# Aquarium_Controller_Diy_Board.net
KiCad netlist of a schematic drawn in EAGLE
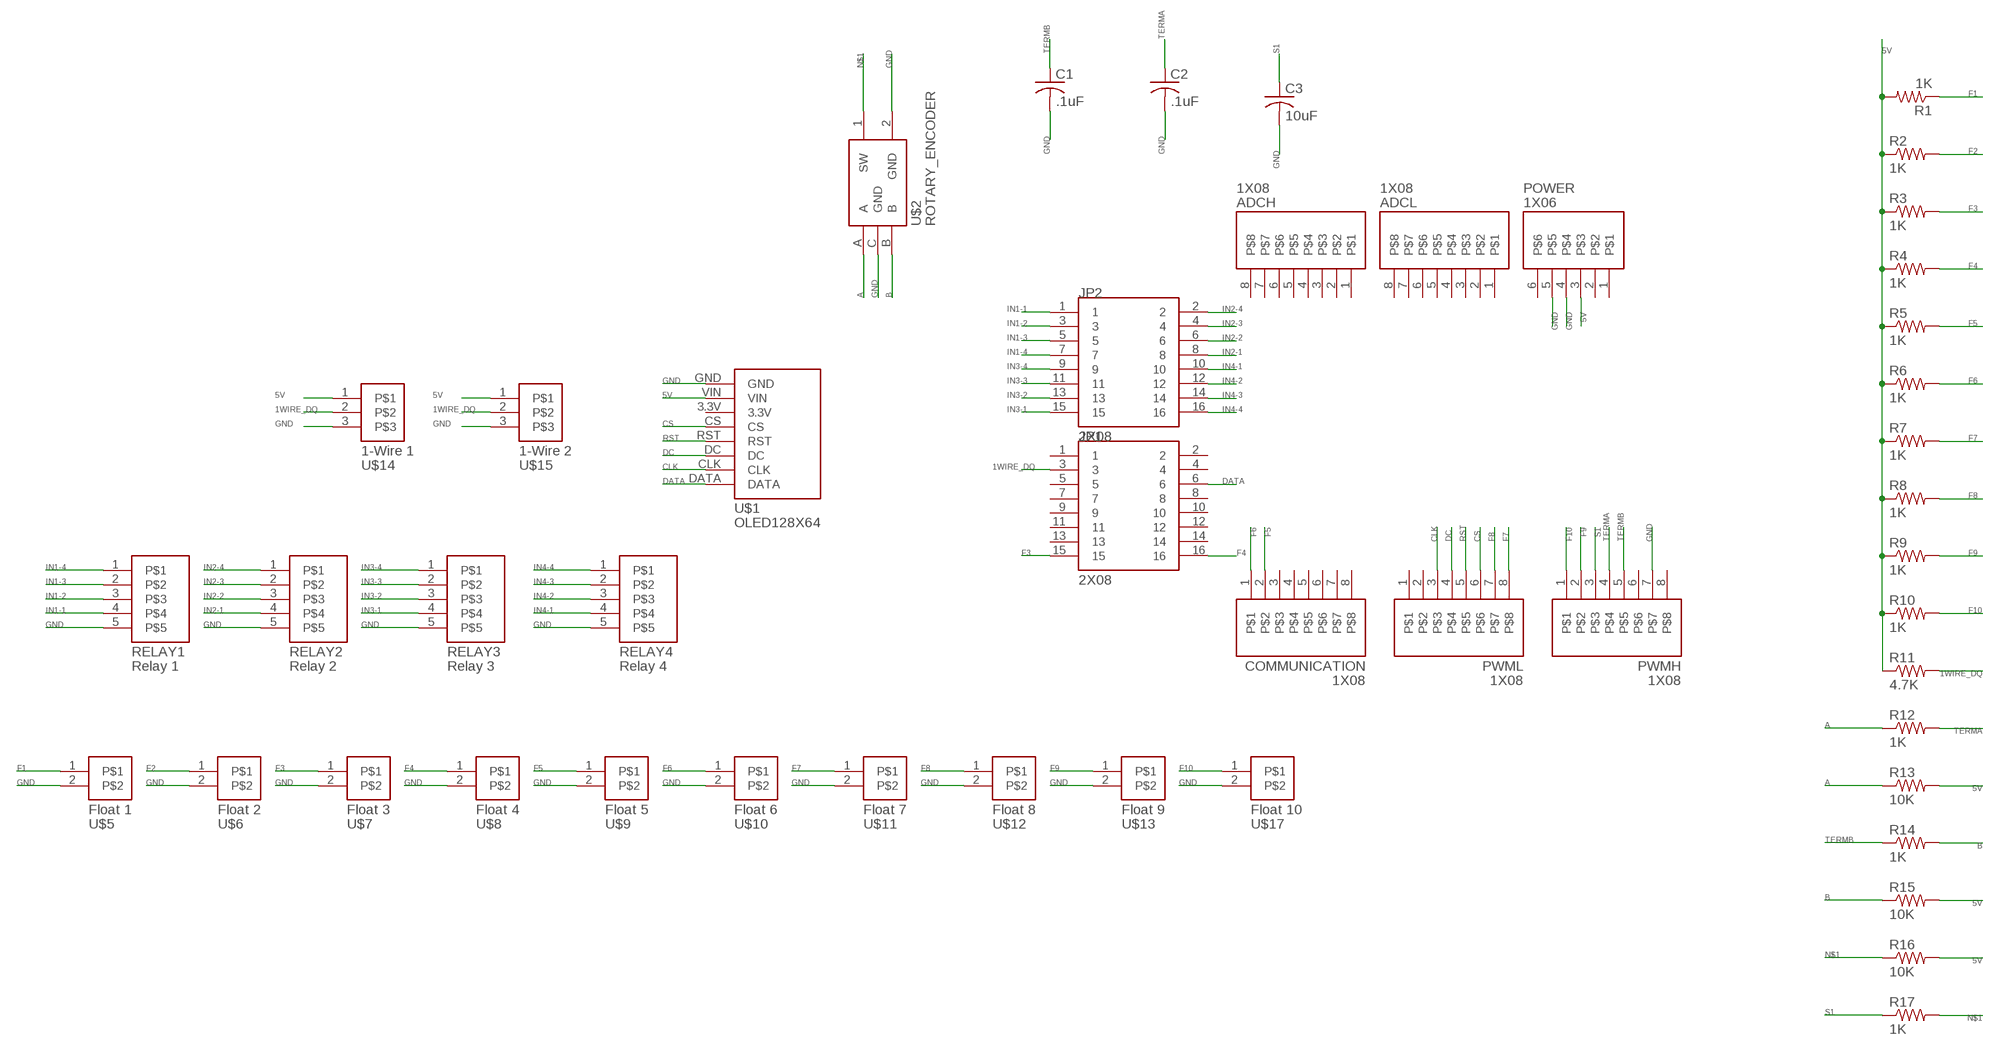
[diagram p0: schematic, sheet 1]

(export (version "E")
  (design (tool "Eeschema 10.0.6"))
  (components
    (comp (ref "ADCH")
      (value "1X08")
      (footprint "eagle-import:1X08_SMT")
      (libsource (lib "eagle-import") (part "1X08"))
    )
    (comp (ref "ADCL")
      (value "1X08")
      (footprint "eagle-import:1X08_SMT")
      (libsource (lib "eagle-import") (part "1X08"))
    )
    (comp (ref "C1")
      (value ".1uF")
      (footprint "eagle-import:C0805K")
      (libsource (lib "eagle-import") (part "C-USC0805K"))
    )
    (comp (ref "C2")
      (value ".1uF")
      (footprint "eagle-import:C0805K")
      (libsource (lib "eagle-import") (part "resistor_C-USC0805K"))
    )
    (comp (ref "C3")
      (value "10uF")
      (footprint "eagle-import:C0805K")
      (libsource (lib "eagle-import") (part "resistor_C-USC0805K"))
    )
    (comp (ref "COMMUNICATION")
      (value "1X08")
      (footprint "eagle-import:1X08_SMT")
      (libsource (lib "eagle-import") (part "1X08"))
    )
    (comp (ref "JP1")
      (value "2X08")
      (footprint "eagle-import:2X08_SMT")
      (libsource (lib "eagle-import") (part "2X08"))
    )
    (comp (ref "JP2")
      (value "2X08")
      (footprint "eagle-import:2X08_SMT")
      (libsource (lib "eagle-import") (part "2X08"))
    )
    (comp (ref "POWER")
      (value "1X06")
      (footprint "eagle-import:1X06_SMT")
      (libsource (lib "eagle-import") (part "1X06"))
    )
    (comp (ref "PWMH")
      (value "1X08")
      (footprint "eagle-import:1X08_SMT")
      (libsource (lib "eagle-import") (part "1X08"))
    )
    (comp (ref "PWML")
      (value "1X08")
      (footprint "eagle-import:1X08_SMT")
      (libsource (lib "eagle-import") (part "1X08"))
    )
    (comp (ref "R1")
      (value "1K")
      (footprint "eagle-import:R0805")
      (libsource (lib "eagle-import") (part "R-US_R0805"))
    )
    (comp (ref "R2")
      (value "1K")
      (footprint "eagle-import:R0805")
      (libsource (lib "eagle-import") (part "R-US_R0805"))
    )
    (comp (ref "R3")
      (value "1K")
      (footprint "eagle-import:R0805")
      (libsource (lib "eagle-import") (part "R-US_R0805"))
    )
    (comp (ref "R4")
      (value "1K")
      (footprint "eagle-import:R0805")
      (libsource (lib "eagle-import") (part "R-US_R0805"))
    )
    (comp (ref "R5")
      (value "1K")
      (footprint "eagle-import:R0805")
      (libsource (lib "eagle-import") (part "R-US_R0805"))
    )
    (comp (ref "R6")
      (value "1K")
      (footprint "eagle-import:R0805")
      (libsource (lib "eagle-import") (part "R-US_R0805"))
    )
    (comp (ref "R7")
      (value "1K")
      (footprint "eagle-import:R0805")
      (libsource (lib "eagle-import") (part "R-US_R0805"))
    )
    (comp (ref "R8")
      (value "1K")
      (footprint "eagle-import:R0805")
      (libsource (lib "eagle-import") (part "R-US_R0805"))
    )
    (comp (ref "R9")
      (value "1K")
      (footprint "eagle-import:R0805")
      (libsource (lib "eagle-import") (part "R-US_R0805"))
    )
    (comp (ref "R10")
      (value "1K")
      (footprint "eagle-import:R0805")
      (libsource (lib "eagle-import") (part "R-US_R0805"))
    )
    (comp (ref "R11")
      (value "4.7K")
      (footprint "eagle-import:R0805")
      (libsource (lib "eagle-import") (part "R-US_R0805"))
    )
    (comp (ref "R12")
      (value "1K")
      (footprint "eagle-import:R0805")
      (libsource (lib "eagle-import") (part "R-US_R0805"))
    )
    (comp (ref "R13")
      (value "10K")
      (footprint "eagle-import:R0805")
      (libsource (lib "eagle-import") (part "R-US_R0805"))
    )
    (comp (ref "R14")
      (value "1K")
      (footprint "eagle-import:R0805")
      (libsource (lib "eagle-import") (part "R-US_R0805"))
    )
    (comp (ref "R15")
      (value "10K")
      (footprint "eagle-import:R0805")
      (libsource (lib "eagle-import") (part "R-US_R0805"))
    )
    (comp (ref "R16")
      (value "10K")
      (footprint "eagle-import:R0805")
      (libsource (lib "eagle-import") (part "R-US_R0805"))
    )
    (comp (ref "R17")
      (value "1K")
      (footprint "eagle-import:R0805")
      (libsource (lib "eagle-import") (part "R-US_R0805"))
    )
    (comp (ref "RELAY1")
      (value "Relay 1")
      (footprint "eagle-import:5PIN-MOLEX-HEADER-W-PEGS")
      (libsource (lib "eagle-import") (part "5PIN"))
    )
    (comp (ref "RELAY2")
      (value "Relay 2")
      (footprint "eagle-import:5PIN-MOLEX-HEADER-W-PEGS")
      (libsource (lib "eagle-import") (part "5PIN"))
    )
    (comp (ref "RELAY3")
      (value "Relay 3")
      (footprint "eagle-import:5PIN-MOLEX-HEADER-W-PEGS")
      (libsource (lib "eagle-import") (part "5PIN"))
    )
    (comp (ref "RELAY4")
      (value "Relay 4")
      (footprint "eagle-import:5PIN-MOLEX-HEADER-W-PEGS")
      (libsource (lib "eagle-import") (part "5PIN"))
    )
    (comp (ref "U$1")
      (value "OLED128X64")
      (footprint "eagle-import:OLED128X64")
      (libsource (lib "eagle-import") (part "OLED128X64"))
    )
    (comp (ref "U$2")
      (value "ROTARY_ENCODER")
      (footprint "eagle-import:PEC11-4215F-S24")
      (libsource (lib "eagle-import") (part "PEC11-4215F-S24"))
    )
    (comp (ref "U$5")
      (value "Float 1")
      (footprint "eagle-import:2PIN-MOLEX-HEADER-W-PEGS")
      (libsource (lib "eagle-import") (part "2PIN"))
    )
    (comp (ref "U$6")
      (value "Float 2")
      (footprint "eagle-import:2PIN-MOLEX-HEADER-W-PEGS")
      (libsource (lib "eagle-import") (part "2PIN"))
    )
    (comp (ref "U$7")
      (value "Float 3")
      (footprint "eagle-import:2PIN-MOLEX-HEADER-W-PEGS")
      (libsource (lib "eagle-import") (part "2PIN"))
    )
    (comp (ref "U$8")
      (value "Float 4")
      (footprint "eagle-import:2PIN-MOLEX-HEADER-W-PEGS")
      (libsource (lib "eagle-import") (part "2PIN"))
    )
    (comp (ref "U$9")
      (value "Float 5")
      (footprint "eagle-import:2PIN-MOLEX-HEADER-W-PEGS")
      (libsource (lib "eagle-import") (part "2PIN"))
    )
    (comp (ref "U$10")
      (value "Float 6")
      (footprint "eagle-import:2PIN-MOLEX-HEADER-W-PEGS")
      (libsource (lib "eagle-import") (part "2PIN"))
    )
    (comp (ref "U$11")
      (value "Float 7")
      (footprint "eagle-import:2PIN-MOLEX-HEADER-W-PEGS")
      (libsource (lib "eagle-import") (part "2PIN"))
    )
    (comp (ref "U$12")
      (value "Float 8")
      (footprint "eagle-import:2PIN-MOLEX-HEADER-W-PEGS")
      (libsource (lib "eagle-import") (part "2PIN"))
    )
    (comp (ref "U$13")
      (value "Float 9")
      (footprint "eagle-import:2PIN-MOLEX-HEADER-W-PEGS")
      (libsource (lib "eagle-import") (part "2PIN"))
    )
    (comp (ref "U$14")
      (value "1-Wire 1")
      (footprint "eagle-import:3PIN-MOLEX-HEADER-W-PEGS")
      (libsource (lib "eagle-import") (part "3PIN"))
    )
    (comp (ref "U$15")
      (value "1-Wire 2")
      (footprint "eagle-import:3PIN-MOLEX-HEADER-W-PEGS")
      (libsource (lib "eagle-import") (part "3PIN"))
    )
    (comp (ref "U$17")
      (value "Float 10")
      (footprint "eagle-import:2PIN-MOLEX-HEADER-W-PEGS")
      (libsource (lib "eagle-import") (part "2PIN"))
    )
  )
  (nets
    (net (code "1") (name "/1WIRE_DQ") (class "Default")
      (node (ref "JP1") (pin "3") (pinfunction "3_3") (pintype "bidirectional"))
      (node (ref "R11") (pin "2") (pinfunction "2_2") (pintype "passive"))
      (node (ref "U$14") (pin "2") (pinfunction "P$2_2") (pintype "bidirectional"))
      (node (ref "U$15") (pin "2") (pinfunction "P$2_2") (pintype "bidirectional"))
    )
    (net (code "2") (name "/5V") (class "Default")
      (node (ref "POWER") (pin "3") (pinfunction "P$3_3") (pintype "bidirectional"))
      (node (ref "R1") (pin "2") (pinfunction "2_2") (pintype "passive"))
      (node (ref "R10") (pin "1") (pinfunction "1_1") (pintype "passive"))
      (node (ref "R11") (pin "1") (pinfunction "1_1") (pintype "passive"))
      (node (ref "R13") (pin "2") (pinfunction "2_2") (pintype "passive"))
      (node (ref "R15") (pin "2") (pinfunction "2_2") (pintype "passive"))
      (node (ref "R16") (pin "2") (pinfunction "2_2") (pintype "passive"))
      (node (ref "R2") (pin "1") (pinfunction "1_1") (pintype "passive"))
      (node (ref "R3") (pin "1") (pinfunction "1_1") (pintype "passive"))
      (node (ref "R4") (pin "1") (pinfunction "1_1") (pintype "passive"))
      (node (ref "R5") (pin "1") (pinfunction "1_1") (pintype "passive"))
      (node (ref "R6") (pin "1") (pinfunction "1_1") (pintype "passive"))
      (node (ref "R7") (pin "1") (pinfunction "1_1") (pintype "passive"))
      (node (ref "R8") (pin "1") (pinfunction "1_1") (pintype "passive"))
      (node (ref "R9") (pin "1") (pinfunction "1_1") (pintype "passive"))
      (node (ref "U$1") (pin "VIN") (pinfunction "VIN_VIN") (pintype "bidirectional"))
      (node (ref "U$14") (pin "1") (pinfunction "P$1_1") (pintype "bidirectional"))
      (node (ref "U$15") (pin "1") (pinfunction "P$1_1") (pintype "bidirectional"))
    )
    (net (code "3") (name "/A") (class "Default")
      (node (ref "R12") (pin "1") (pinfunction "1_1") (pintype "passive"))
      (node (ref "R13") (pin "1") (pinfunction "1_1") (pintype "passive"))
      (node (ref "U$2") (pin "A") (pinfunction "A_A") (pintype "bidirectional"))
    )
    (net (code "4") (name "/B") (class "Default")
      (node (ref "R14") (pin "2") (pinfunction "2_2") (pintype "passive"))
      (node (ref "R15") (pin "1") (pinfunction "1_1") (pintype "passive"))
      (node (ref "U$2") (pin "B") (pinfunction "B_B") (pintype "bidirectional"))
    )
    (net (code "5") (name "/CLK") (class "Default")
      (node (ref "PWML") (pin "3") (pinfunction "P$3_3") (pintype "bidirectional"))
      (node (ref "U$1") (pin "CLK") (pinfunction "CLK_CLK") (pintype "bidirectional"))
    )
    (net (code "6") (name "/CS") (class "Default")
      (node (ref "PWML") (pin "6") (pinfunction "P$6_6") (pintype "bidirectional"))
      (node (ref "U$1") (pin "CS") (pinfunction "CS_CS") (pintype "bidirectional"))
    )
    (net (code "7") (name "/DATA") (class "Default")
      (node (ref "JP1") (pin "6") (pinfunction "6_6") (pintype "bidirectional"))
      (node (ref "U$1") (pin "DATA") (pinfunction "DATA_DATA") (pintype "bidirectional"))
    )
    (net (code "8") (name "/DC") (class "Default")
      (node (ref "PWML") (pin "4") (pinfunction "P$4_4") (pintype "bidirectional"))
      (node (ref "U$1") (pin "DC") (pinfunction "DC_DC") (pintype "bidirectional"))
    )
    (net (code "9") (name "/F1") (class "Default")
      (node (ref "R1") (pin "1") (pinfunction "1_1") (pintype "passive"))
      (node (ref "U$5") (pin "1") (pinfunction "P$1_1") (pintype "bidirectional"))
    )
    (net (code "10") (name "/F2") (class "Default")
      (node (ref "R2") (pin "2") (pinfunction "2_2") (pintype "passive"))
      (node (ref "U$6") (pin "1") (pinfunction "P$1_1") (pintype "bidirectional"))
    )
    (net (code "11") (name "/F3") (class "Default")
      (node (ref "JP1") (pin "15") (pinfunction "15_15") (pintype "bidirectional"))
      (node (ref "R3") (pin "2") (pinfunction "2_2") (pintype "passive"))
      (node (ref "U$7") (pin "1") (pinfunction "P$1_1") (pintype "bidirectional"))
    )
    (net (code "12") (name "/F4") (class "Default")
      (node (ref "JP1") (pin "16") (pinfunction "16_16") (pintype "bidirectional"))
      (node (ref "R4") (pin "2") (pinfunction "2_2") (pintype "passive"))
      (node (ref "U$8") (pin "1") (pinfunction "P$1_1") (pintype "bidirectional"))
    )
    (net (code "13") (name "/F5") (class "Default")
      (node (ref "COMMUNICATION") (pin "2") (pinfunction "P$2_2") (pintype "bidirectional"))
      (node (ref "R5") (pin "2") (pinfunction "2_2") (pintype "passive"))
      (node (ref "U$9") (pin "1") (pinfunction "P$1_1") (pintype "bidirectional"))
    )
    (net (code "14") (name "/F6") (class "Default")
      (node (ref "COMMUNICATION") (pin "1") (pinfunction "P$1_1") (pintype "bidirectional"))
      (node (ref "R6") (pin "2") (pinfunction "2_2") (pintype "passive"))
      (node (ref "U$10") (pin "1") (pinfunction "P$1_1") (pintype "bidirectional"))
    )
    (net (code "15") (name "/F7") (class "Default")
      (node (ref "PWML") (pin "8") (pinfunction "P$8_8") (pintype "bidirectional"))
      (node (ref "R7") (pin "2") (pinfunction "2_2") (pintype "passive"))
      (node (ref "U$11") (pin "1") (pinfunction "P$1_1") (pintype "bidirectional"))
    )
    (net (code "16") (name "/F8") (class "Default")
      (node (ref "PWML") (pin "7") (pinfunction "P$7_7") (pintype "bidirectional"))
      (node (ref "R8") (pin "2") (pinfunction "2_2") (pintype "passive"))
      (node (ref "U$12") (pin "1") (pinfunction "P$1_1") (pintype "bidirectional"))
    )
    (net (code "17") (name "/F9") (class "Default")
      (node (ref "PWMH") (pin "2") (pinfunction "P$2_2") (pintype "bidirectional"))
      (node (ref "R9") (pin "2") (pinfunction "2_2") (pintype "passive"))
      (node (ref "U$13") (pin "1") (pinfunction "P$1_1") (pintype "bidirectional"))
    )
    (net (code "18") (name "/F10") (class "Default")
      (node (ref "PWMH") (pin "1") (pinfunction "P$1_1") (pintype "bidirectional"))
      (node (ref "R10") (pin "2") (pinfunction "2_2") (pintype "passive"))
      (node (ref "U$17") (pin "1") (pinfunction "P$1_1") (pintype "bidirectional"))
    )
    (net (code "19") (name "/GND") (class "Default")
      (node (ref "C1") (pin "2") (pinfunction "2_2") (pintype "passive"))
      (node (ref "C2") (pin "2") (pinfunction "2_2") (pintype "passive"))
      (node (ref "C3") (pin "2") (pinfunction "2_2") (pintype "passive"))
      (node (ref "POWER") (pin "4") (pinfunction "P$4_4") (pintype "bidirectional"))
      (node (ref "POWER") (pin "5") (pinfunction "P$5_5") (pintype "bidirectional"))
      (node (ref "PWMH") (pin "7") (pinfunction "P$7_7") (pintype "bidirectional"))
      (node (ref "RELAY1") (pin "5") (pinfunction "P$5_5") (pintype "bidirectional"))
      (node (ref "RELAY2") (pin "5") (pinfunction "P$5_5") (pintype "bidirectional"))
      (node (ref "RELAY3") (pin "5") (pinfunction "P$5_5") (pintype "bidirectional"))
      (node (ref "RELAY4") (pin "5") (pinfunction "P$5_5") (pintype "bidirectional"))
      (node (ref "U$1") (pin "GND") (pinfunction "GND_GND") (pintype "bidirectional"))
      (node (ref "U$10") (pin "2") (pinfunction "P$2_2") (pintype "bidirectional"))
      (node (ref "U$11") (pin "2") (pinfunction "P$2_2") (pintype "bidirectional"))
      (node (ref "U$12") (pin "2") (pinfunction "P$2_2") (pintype "bidirectional"))
      (node (ref "U$13") (pin "2") (pinfunction "P$2_2") (pintype "bidirectional"))
      (node (ref "U$14") (pin "3") (pinfunction "P$3_3") (pintype "bidirectional"))
      (node (ref "U$15") (pin "3") (pinfunction "P$3_3") (pintype "bidirectional"))
      (node (ref "U$17") (pin "2") (pinfunction "P$2_2") (pintype "bidirectional"))
      (node (ref "U$2") (pin "2") (pinfunction "GND_2") (pintype "bidirectional"))
      (node (ref "U$2") (pin "C") (pinfunction "GND_C") (pintype "bidirectional"))
      (node (ref "U$5") (pin "2") (pinfunction "P$2_2") (pintype "bidirectional"))
      (node (ref "U$6") (pin "2") (pinfunction "P$2_2") (pintype "bidirectional"))
      (node (ref "U$7") (pin "2") (pinfunction "P$2_2") (pintype "bidirectional"))
      (node (ref "U$8") (pin "2") (pinfunction "P$2_2") (pintype "bidirectional"))
      (node (ref "U$9") (pin "2") (pinfunction "P$2_2") (pintype "bidirectional"))
    )
    (net (code "20") (name "/IN1-1") (class "Default")
      (node (ref "JP2") (pin "1") (pinfunction "1_1") (pintype "bidirectional"))
      (node (ref "RELAY1") (pin "4") (pinfunction "P$4_4") (pintype "bidirectional"))
    )
    (net (code "21") (name "/IN1-2") (class "Default")
      (node (ref "JP2") (pin "3") (pinfunction "3_3") (pintype "bidirectional"))
      (node (ref "RELAY1") (pin "3") (pinfunction "P$3_3") (pintype "bidirectional"))
    )
    (net (code "22") (name "/IN1-3") (class "Default")
      (node (ref "JP2") (pin "5") (pinfunction "5_5") (pintype "bidirectional"))
      (node (ref "RELAY1") (pin "2") (pinfunction "P$2_2") (pintype "bidirectional"))
    )
    (net (code "23") (name "/IN1-4") (class "Default")
      (node (ref "JP2") (pin "7") (pinfunction "7_7") (pintype "bidirectional"))
      (node (ref "RELAY1") (pin "1") (pinfunction "P$1_1") (pintype "bidirectional"))
    )
    (net (code "24") (name "/IN2-1") (class "Default")
      (node (ref "JP2") (pin "8") (pinfunction "8_8") (pintype "bidirectional"))
      (node (ref "RELAY2") (pin "4") (pinfunction "P$4_4") (pintype "bidirectional"))
    )
    (net (code "25") (name "/IN2-2") (class "Default")
      (node (ref "JP2") (pin "6") (pinfunction "6_6") (pintype "bidirectional"))
      (node (ref "RELAY2") (pin "3") (pinfunction "P$3_3") (pintype "bidirectional"))
    )
    (net (code "26") (name "/IN2-3") (class "Default")
      (node (ref "JP2") (pin "4") (pinfunction "4_4") (pintype "bidirectional"))
      (node (ref "RELAY2") (pin "2") (pinfunction "P$2_2") (pintype "bidirectional"))
    )
    (net (code "27") (name "/IN2-4") (class "Default")
      (node (ref "JP2") (pin "2") (pinfunction "2_2") (pintype "bidirectional"))
      (node (ref "RELAY2") (pin "1") (pinfunction "P$1_1") (pintype "bidirectional"))
    )
    (net (code "28") (name "/IN3-1") (class "Default")
      (node (ref "JP2") (pin "15") (pinfunction "15_15") (pintype "bidirectional"))
      (node (ref "RELAY3") (pin "4") (pinfunction "P$4_4") (pintype "bidirectional"))
    )
    (net (code "29") (name "/IN3-2") (class "Default")
      (node (ref "JP2") (pin "13") (pinfunction "13_13") (pintype "bidirectional"))
      (node (ref "RELAY3") (pin "3") (pinfunction "P$3_3") (pintype "bidirectional"))
    )
    (net (code "30") (name "/IN3-3") (class "Default")
      (node (ref "JP2") (pin "11") (pinfunction "11_11") (pintype "bidirectional"))
      (node (ref "RELAY3") (pin "2") (pinfunction "P$2_2") (pintype "bidirectional"))
    )
    (net (code "31") (name "/IN3-4") (class "Default")
      (node (ref "JP2") (pin "9") (pinfunction "9_9") (pintype "bidirectional"))
      (node (ref "RELAY3") (pin "1") (pinfunction "P$1_1") (pintype "bidirectional"))
    )
    (net (code "32") (name "/IN4-1") (class "Default")
      (node (ref "JP2") (pin "10") (pinfunction "10_10") (pintype "bidirectional"))
      (node (ref "RELAY4") (pin "4") (pinfunction "P$4_4") (pintype "bidirectional"))
    )
    (net (code "33") (name "/IN4-2") (class "Default")
      (node (ref "JP2") (pin "12") (pinfunction "12_12") (pintype "bidirectional"))
      (node (ref "RELAY4") (pin "3") (pinfunction "P$3_3") (pintype "bidirectional"))
    )
    (net (code "34") (name "/IN4-3") (class "Default")
      (node (ref "JP2") (pin "14") (pinfunction "14_14") (pintype "bidirectional"))
      (node (ref "RELAY4") (pin "2") (pinfunction "P$2_2") (pintype "bidirectional"))
    )
    (net (code "35") (name "/IN4-4") (class "Default")
      (node (ref "JP2") (pin "16") (pinfunction "16_16") (pintype "bidirectional"))
      (node (ref "RELAY4") (pin "1") (pinfunction "P$1_1") (pintype "bidirectional"))
    )
    (net (code "36") (name "/N$1") (class "Default")
      (node (ref "R16") (pin "1") (pinfunction "1_1") (pintype "passive"))
      (node (ref "R17") (pin "2") (pinfunction "2_2") (pintype "passive"))
      (node (ref "U$2") (pin "1") (pinfunction "SW_1") (pintype "bidirectional"))
    )
    (net (code "37") (name "/RST") (class "Default")
      (node (ref "PWML") (pin "5") (pinfunction "P$5_5") (pintype "bidirectional"))
      (node (ref "U$1") (pin "RST") (pinfunction "RST_RST") (pintype "bidirectional"))
    )
    (net (code "38") (name "/S1") (class "Default")
      (node (ref "C3") (pin "1") (pinfunction "1_1") (pintype "passive"))
      (node (ref "PWMH") (pin "3") (pinfunction "P$3_3") (pintype "bidirectional"))
      (node (ref "R17") (pin "1") (pinfunction "1_1") (pintype "passive"))
    )
    (net (code "39") (name "/TERMA") (class "Default")
      (node (ref "C2") (pin "1") (pinfunction "1_1") (pintype "passive"))
      (node (ref "PWMH") (pin "4") (pinfunction "P$4_4") (pintype "bidirectional"))
      (node (ref "R12") (pin "2") (pinfunction "2_2") (pintype "passive"))
    )
    (net (code "40") (name "/TERMB") (class "Default")
      (node (ref "C1") (pin "1") (pinfunction "1_1") (pintype "passive"))
      (node (ref "PWMH") (pin "5") (pinfunction "P$5_5") (pintype "bidirectional"))
      (node (ref "R14") (pin "1") (pinfunction "1_1") (pintype "passive"))
    )
    (net (code "41") (name "unconnected-(ADCH-P$1-Pad1)") (class "Default")
      (node (ref "ADCH") (pin "1") (pinfunction "P$1_1") (pintype "bidirectional"))
    )
    (net (code "42") (name "unconnected-(ADCH-P$2-Pad2)") (class "Default")
      (node (ref "ADCH") (pin "2") (pinfunction "P$2_2") (pintype "bidirectional"))
    )
    (net (code "43") (name "unconnected-(ADCH-P$3-Pad3)") (class "Default")
      (node (ref "ADCH") (pin "3") (pinfunction "P$3_3") (pintype "bidirectional"))
    )
    (net (code "44") (name "unconnected-(ADCH-P$4-Pad4)") (class "Default")
      (node (ref "ADCH") (pin "4") (pinfunction "P$4_4") (pintype "bidirectional"))
    )
    (net (code "45") (name "unconnected-(ADCH-P$5-Pad5)") (class "Default")
      (node (ref "ADCH") (pin "5") (pinfunction "P$5_5") (pintype "bidirectional"))
    )
    (net (code "46") (name "unconnected-(ADCH-P$6-Pad6)") (class "Default")
      (node (ref "ADCH") (pin "6") (pinfunction "P$6_6") (pintype "bidirectional"))
    )
    (net (code "47") (name "unconnected-(ADCH-P$7-Pad7)") (class "Default")
      (node (ref "ADCH") (pin "7") (pinfunction "P$7_7") (pintype "bidirectional"))
    )
    (net (code "48") (name "unconnected-(ADCH-P$8-Pad8)") (class "Default")
      (node (ref "ADCH") (pin "8") (pinfunction "P$8_8") (pintype "bidirectional"))
    )
    (net (code "49") (name "unconnected-(ADCL-P$1-Pad1)") (class "Default")
      (node (ref "ADCL") (pin "1") (pinfunction "P$1_1") (pintype "bidirectional"))
    )
    (net (code "50") (name "unconnected-(ADCL-P$2-Pad2)") (class "Default")
      (node (ref "ADCL") (pin "2") (pinfunction "P$2_2") (pintype "bidirectional"))
    )
    (net (code "51") (name "unconnected-(ADCL-P$3-Pad3)") (class "Default")
      (node (ref "ADCL") (pin "3") (pinfunction "P$3_3") (pintype "bidirectional"))
    )
    (net (code "52") (name "unconnected-(ADCL-P$4-Pad4)") (class "Default")
      (node (ref "ADCL") (pin "4") (pinfunction "P$4_4") (pintype "bidirectional"))
    )
    (net (code "53") (name "unconnected-(ADCL-P$5-Pad5)") (class "Default")
      (node (ref "ADCL") (pin "5") (pinfunction "P$5_5") (pintype "bidirectional"))
    )
    (net (code "54") (name "unconnected-(ADCL-P$6-Pad6)") (class "Default")
      (node (ref "ADCL") (pin "6") (pinfunction "P$6_6") (pintype "bidirectional"))
    )
    (net (code "55") (name "unconnected-(ADCL-P$7-Pad7)") (class "Default")
      (node (ref "ADCL") (pin "7") (pinfunction "P$7_7") (pintype "bidirectional"))
    )
    (net (code "56") (name "unconnected-(ADCL-P$8-Pad8)") (class "Default")
      (node (ref "ADCL") (pin "8") (pinfunction "P$8_8") (pintype "bidirectional"))
    )
    (net (code "57") (name "unconnected-(COMMUNICATION-P$3-Pad3)") (class "Default")
      (node (ref "COMMUNICATION") (pin "3") (pinfunction "P$3_3") (pintype "bidirectional"))
    )
    (net (code "58") (name "unconnected-(COMMUNICATION-P$4-Pad4)") (class "Default")
      (node (ref "COMMUNICATION") (pin "4") (pinfunction "P$4_4") (pintype "bidirectional"))
    )
    (net (code "59") (name "unconnected-(COMMUNICATION-P$5-Pad5)") (class "Default")
      (node (ref "COMMUNICATION") (pin "5") (pinfunction "P$5_5") (pintype "bidirectional"))
    )
    (net (code "60") (name "unconnected-(COMMUNICATION-P$6-Pad6)") (class "Default")
      (node (ref "COMMUNICATION") (pin "6") (pinfunction "P$6_6") (pintype "bidirectional"))
    )
    (net (code "61") (name "unconnected-(COMMUNICATION-P$7-Pad7)") (class "Default")
      (node (ref "COMMUNICATION") (pin "7") (pinfunction "P$7_7") (pintype "bidirectional"))
    )
    (net (code "62") (name "unconnected-(COMMUNICATION-P$8-Pad8)") (class "Default")
      (node (ref "COMMUNICATION") (pin "8") (pinfunction "P$8_8") (pintype "bidirectional"))
    )
    (net (code "63") (name "unconnected-(JP1-Pad1)") (class "Default")
      (node (ref "JP1") (pin "1") (pinfunction "1_1") (pintype "bidirectional"))
    )
    (net (code "64") (name "unconnected-(JP1-Pad2)") (class "Default")
      (node (ref "JP1") (pin "2") (pinfunction "2_2") (pintype "bidirectional"))
    )
    (net (code "65") (name "unconnected-(JP1-Pad4)") (class "Default")
      (node (ref "JP1") (pin "4") (pinfunction "4_4") (pintype "bidirectional"))
    )
    (net (code "66") (name "unconnected-(JP1-Pad5)") (class "Default")
      (node (ref "JP1") (pin "5") (pinfunction "5_5") (pintype "bidirectional"))
    )
    (net (code "67") (name "unconnected-(JP1-Pad7)") (class "Default")
      (node (ref "JP1") (pin "7") (pinfunction "7_7") (pintype "bidirectional"))
    )
    (net (code "68") (name "unconnected-(JP1-Pad8)") (class "Default")
      (node (ref "JP1") (pin "8") (pinfunction "8_8") (pintype "bidirectional"))
    )
    (net (code "69") (name "unconnected-(JP1-Pad9)") (class "Default")
      (node (ref "JP1") (pin "9") (pinfunction "9_9") (pintype "bidirectional"))
    )
    (net (code "70") (name "unconnected-(JP1-Pad10)") (class "Default")
      (node (ref "JP1") (pin "10") (pinfunction "10_10") (pintype "bidirectional"))
    )
    (net (code "71") (name "unconnected-(JP1-Pad11)") (class "Default")
      (node (ref "JP1") (pin "11") (pinfunction "11_11") (pintype "bidirectional"))
    )
    (net (code "72") (name "unconnected-(JP1-Pad12)") (class "Default")
      (node (ref "JP1") (pin "12") (pinfunction "12_12") (pintype "bidirectional"))
    )
    (net (code "73") (name "unconnected-(JP1-Pad13)") (class "Default")
      (node (ref "JP1") (pin "13") (pinfunction "13_13") (pintype "bidirectional"))
    )
    (net (code "74") (name "unconnected-(JP1-Pad14)") (class "Default")
      (node (ref "JP1") (pin "14") (pinfunction "14_14") (pintype "bidirectional"))
    )
    (net (code "75") (name "unconnected-(POWER-P$1-Pad1)") (class "Default")
      (node (ref "POWER") (pin "1") (pinfunction "P$1_1") (pintype "bidirectional"))
    )
    (net (code "76") (name "unconnected-(POWER-P$2-Pad2)") (class "Default")
      (node (ref "POWER") (pin "2") (pinfunction "P$2_2") (pintype "bidirectional"))
    )
    (net (code "77") (name "unconnected-(POWER-P$6-Pad6)") (class "Default")
      (node (ref "POWER") (pin "6") (pinfunction "P$6_6") (pintype "bidirectional"))
    )
    (net (code "78") (name "unconnected-(PWMH-P$6-Pad6)") (class "Default")
      (node (ref "PWMH") (pin "6") (pinfunction "P$6_6") (pintype "bidirectional"))
    )
    (net (code "79") (name "unconnected-(PWMH-P$8-Pad8)") (class "Default")
      (node (ref "PWMH") (pin "8") (pinfunction "P$8_8") (pintype "bidirectional"))
    )
    (net (code "80") (name "unconnected-(PWML-P$1-Pad1)") (class "Default")
      (node (ref "PWML") (pin "1") (pinfunction "P$1_1") (pintype "bidirectional"))
    )
    (net (code "81") (name "unconnected-(PWML-P$2-Pad2)") (class "Default")
      (node (ref "PWML") (pin "2") (pinfunction "P$2_2") (pintype "bidirectional"))
    )
    (net (code "82") (name "unconnected-(U$1-Pad3.3V)") (class "Default")
      (node (ref "U$1") (pin "3.3V") (pinfunction "3.3V_3.3V") (pintype "bidirectional"))
    )
  )
)
